# RadioAdapterBoardV4_0.net
KiCad netlist of a schematic drawn in EAGLE
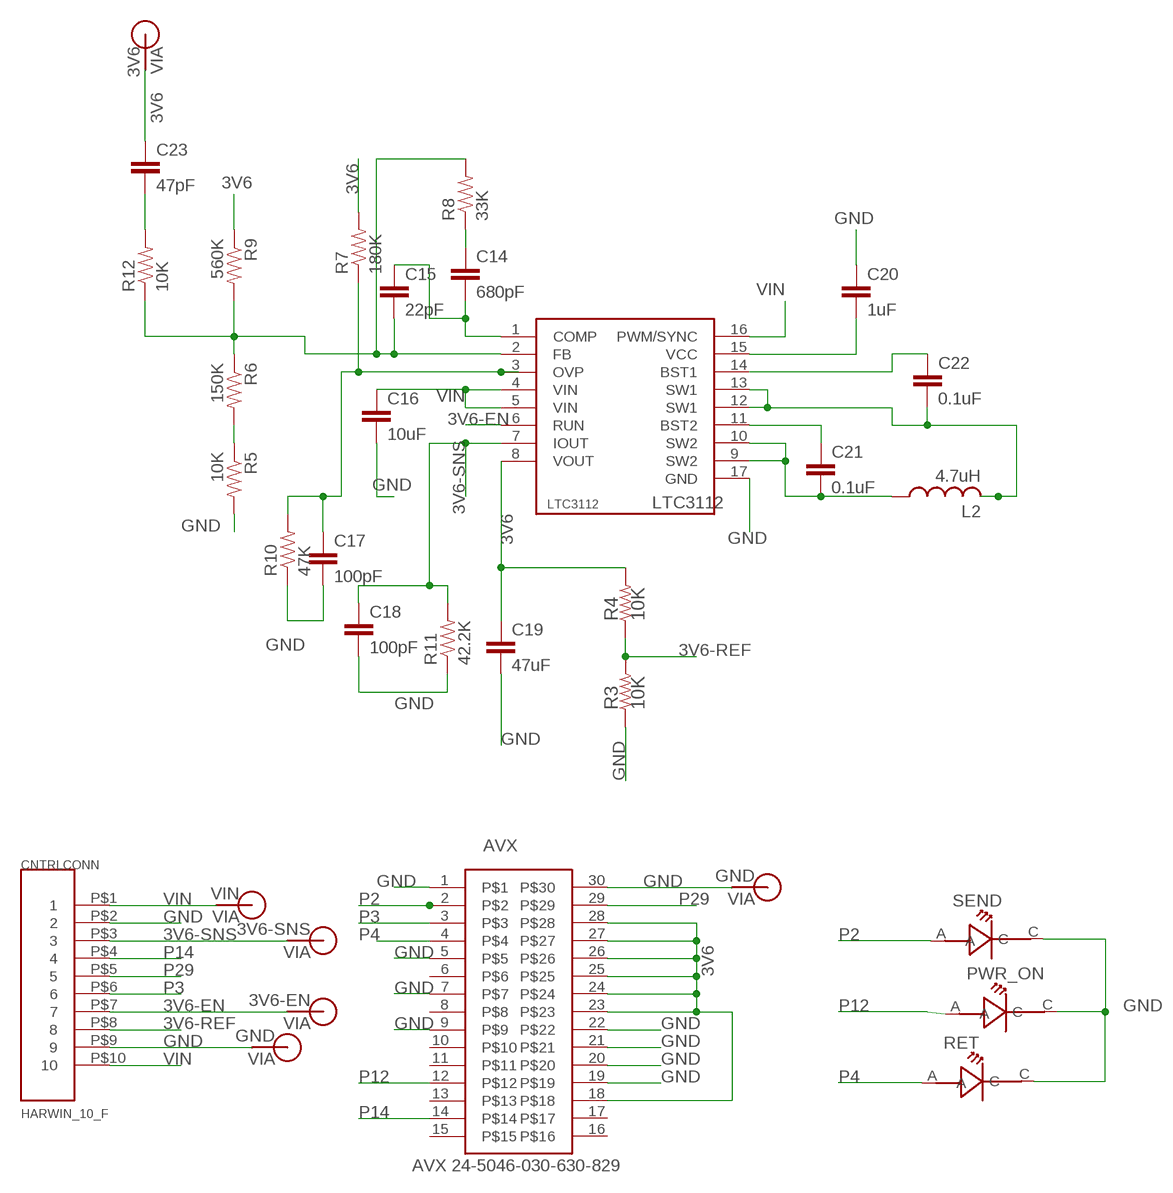
[diagram p0: schematic, sheet 1]

(export (version "E")
  (design (tool "Eeschema 10.0.6"))
  (components
    (comp (ref "AVX")
      (value "AVX-24-5046-030-630-829")
      (footprint "eagle-import:AVX-24-5046-630-829")
      (libsource (lib "eagle-import") (part "AVX-24-5046-030-630-829"))
    )
    (comp (ref "C14")
      (value "680pF")
      (footprint "eagle-import:0805")
      (libsource (lib "eagle-import") (part "CAP0805"))
    )
    (comp (ref "C15")
      (value "22pF")
      (footprint "eagle-import:0805")
      (libsource (lib "eagle-import") (part "CAP0805"))
    )
    (comp (ref "C16")
      (value "10uF")
      (footprint "eagle-import:0805")
      (libsource (lib "eagle-import") (part "CAP0805"))
    )
    (comp (ref "C17")
      (value "100pF")
      (footprint "eagle-import:0805")
      (libsource (lib "eagle-import") (part "CAP0805"))
    )
    (comp (ref "C18")
      (value "100pF")
      (footprint "eagle-import:0805")
      (libsource (lib "eagle-import") (part "CAP0805"))
    )
    (comp (ref "C19")
      (value "47uF")
      (footprint "eagle-import:0805")
      (libsource (lib "eagle-import") (part "CAP0805"))
    )
    (comp (ref "C20")
      (value "1uF")
      (footprint "eagle-import:0805")
      (libsource (lib "eagle-import") (part "CAP0805"))
    )
    (comp (ref "C21")
      (value "0.1uF")
      (footprint "eagle-import:0805")
      (libsource (lib "eagle-import") (part "CAP0805"))
    )
    (comp (ref "C22")
      (value "0.1uF")
      (footprint "eagle-import:0805")
      (libsource (lib "eagle-import") (part "CAP0805"))
    )
    (comp (ref "C23")
      (value "47pF")
      (footprint "eagle-import:0805")
      (libsource (lib "eagle-import") (part "CAP0805"))
    )
    (comp (ref "CNTRLCONN")
      (value "HARWIN_10_F")
      (footprint "eagle-import:HARWIN_DATAMATE_10_F")
      (libsource (lib "eagle-import") (part "HARWIN_10_F"))
    )
    (comp (ref "L2")
      (value "4.7uH")
      (footprint "eagle-import:L3225M")
      (libsource (lib "eagle-import") (part "L-USL3225M"))
    )
    (comp (ref "LTC3112")
      (value "LTC3112")
      (footprint "eagle-import:DHD16")
      (libsource (lib "eagle-import") (part "LTC3112"))
    )
    (comp (ref "PWR_ON")
      (value "LT-T673-Q1R2-25-Z")
      (footprint "eagle-import:PLCC-2")
      (libsource (lib "eagle-import") (part "LT-T673-Q1R2-25-Z"))
    )
    (comp (ref "R3")
      (value "10K")
      (footprint "eagle-import:0805")
      (libsource (lib "eagle-import") (part "RES0805"))
    )
    (comp (ref "R4")
      (value "10K")
      (footprint "eagle-import:0805")
      (libsource (lib "eagle-import") (part "RES0805"))
    )
    (comp (ref "R5")
      (value "10K")
      (footprint "eagle-import:0805")
      (libsource (lib "eagle-import") (part "RESISTOR"))
    )
    (comp (ref "R6")
      (value "150K")
      (footprint "eagle-import:0805")
      (libsource (lib "eagle-import") (part "RESISTOR"))
    )
    (comp (ref "R7")
      (value "180K")
      (footprint "eagle-import:0805")
      (libsource (lib "eagle-import") (part "RESISTOR"))
    )
    (comp (ref "R8")
      (value "33K")
      (footprint "eagle-import:0805")
      (libsource (lib "eagle-import") (part "RESISTOR"))
    )
    (comp (ref "R9")
      (value "560K")
      (footprint "eagle-import:0805")
      (libsource (lib "eagle-import") (part "RESISTOR"))
    )
    (comp (ref "R10")
      (value "47K")
      (footprint "eagle-import:0805")
      (libsource (lib "eagle-import") (part "RESISTOR"))
    )
    (comp (ref "R11")
      (value "42.2K")
      (footprint "eagle-import:0805")
      (libsource (lib "eagle-import") (part "RESISTOR"))
    )
    (comp (ref "R12")
      (value "10K")
      (footprint "eagle-import:0805")
      (libsource (lib "eagle-import") (part "RESISTOR"))
    )
    (comp (ref "RET")
      (value "LT-T673-Q1R2-25-Z")
      (footprint "eagle-import:PLCC-2")
      (libsource (lib "eagle-import") (part "LT-T673-Q1R2-25-Z"))
    )
    (comp (ref "SEND")
      (value "LT-T673-Q1R2-25-Z")
      (footprint "eagle-import:PLCC-2")
      (libsource (lib "eagle-import") (part "LT-T673-Q1R2-25-Z"))
    )
    (comp (ref "V1")
      (value "VIN")
      (footprint "eagle-import:VIA-60MIL-SQ")
      (libsource (lib "eagle-import") (part "VIA60MIL-SQ"))
    )
    (comp (ref "V2")
      (value "3V6-SNS")
      (footprint "eagle-import:VIA-60MIL-SQ")
      (libsource (lib "eagle-import") (part "VIA60MIL-SQ"))
    )
    (comp (ref "V3")
      (value "GND")
      (footprint "eagle-import:VIA-60MIL-SQ")
      (libsource (lib "eagle-import") (part "VIA60MIL-SQ"))
    )
    (comp (ref "V4")
      (value "GND")
      (footprint "eagle-import:VIA-60MIL-SQ")
      (libsource (lib "eagle-import") (part "VIA60MIL-SQ"))
    )
    (comp (ref "V5")
      (value "3V6")
      (footprint "eagle-import:VIA-60MIL-SQ")
      (libsource (lib "eagle-import") (part "VIA60MIL-SQ"))
    )
    (comp (ref "V6")
      (value "3V6-EN")
      (footprint "eagle-import:VIA-60MIL-SQ")
      (libsource (lib "eagle-import") (part "VIA60MIL-SQ"))
    )
  )
  (nets
    (net (code "1") (name "/3V6") (class "Default")
      (node (ref "AVX") (pin "18") (pinfunction "P$18_18") (pintype "bidirectional"))
      (node (ref "AVX") (pin "23") (pinfunction "P$23_23") (pintype "bidirectional"))
      (node (ref "AVX") (pin "24") (pinfunction "P$24_24") (pintype "bidirectional"))
      (node (ref "AVX") (pin "25") (pinfunction "P$25_25") (pintype "bidirectional"))
      (node (ref "AVX") (pin "26") (pinfunction "P$26_26") (pintype "bidirectional"))
      (node (ref "AVX") (pin "27") (pinfunction "P$27_27") (pintype "bidirectional"))
      (node (ref "AVX") (pin "28") (pinfunction "P$28_28") (pintype "bidirectional"))
      (node (ref "C19") (pin "1") (pinfunction "1_1") (pintype "passive"))
      (node (ref "C23") (pin "1") (pinfunction "1_1") (pintype "passive"))
      (node (ref "LTC3112") (pin "8") (pinfunction "VOUT_8") (pintype "bidirectional"))
      (node (ref "R4") (pin "2") (pinfunction "2_2") (pintype "passive"))
      (node (ref "R7") (pin "2") (pinfunction "2_2") (pintype "passive"))
      (node (ref "R9") (pin "1") (pinfunction "1_1") (pintype "passive"))
      (node (ref "V5") (pin "P$1") (pinfunction "P$1_P$1") (pintype "bidirectional"))
    )
    (net (code "2") (name "/3V6-EN") (class "Default")
      (node (ref "CNTRLCONN") (pin "P$7") (pinfunction "7_P$7") (pintype "bidirectional"))
      (node (ref "LTC3112") (pin "6") (pinfunction "RUN_6") (pintype "bidirectional"))
      (node (ref "V6") (pin "P$1") (pinfunction "P$1_P$1") (pintype "bidirectional"))
    )
    (net (code "3") (name "/3V6-REF") (class "Default")
      (node (ref "CNTRLCONN") (pin "P$8") (pinfunction "8_P$8") (pintype "bidirectional"))
      (node (ref "R3") (pin "2") (pinfunction "2_2") (pintype "passive"))
      (node (ref "R4") (pin "1") (pinfunction "1_1") (pintype "passive"))
    )
    (net (code "4") (name "/3V6-SNS") (class "Default")
      (node (ref "C18") (pin "1") (pinfunction "1_1") (pintype "passive"))
      (node (ref "CNTRLCONN") (pin "P$3") (pinfunction "3_P$3") (pintype "bidirectional"))
      (node (ref "LTC3112") (pin "7") (pinfunction "IOUT_7") (pintype "bidirectional"))
      (node (ref "R11") (pin "2") (pinfunction "2_2") (pintype "passive"))
      (node (ref "V2") (pin "P$1") (pinfunction "P$1_P$1") (pintype "bidirectional"))
    )
    (net (code "5") (name "/GND") (class "Default")
      (node (ref "AVX") (pin "1") (pinfunction "P$1_1") (pintype "bidirectional"))
      (node (ref "AVX") (pin "19") (pinfunction "P$19_19") (pintype "bidirectional"))
      (node (ref "AVX") (pin "20") (pinfunction "P$20_20") (pintype "bidirectional"))
      (node (ref "AVX") (pin "21") (pinfunction "P$21_21") (pintype "bidirectional"))
      (node (ref "AVX") (pin "22") (pinfunction "P$22_22") (pintype "bidirectional"))
      (node (ref "AVX") (pin "30") (pinfunction "P$30_30") (pintype "bidirectional"))
      (node (ref "AVX") (pin "5") (pinfunction "P$5_5") (pintype "bidirectional"))
      (node (ref "AVX") (pin "7") (pinfunction "P$7_7") (pintype "bidirectional"))
      (node (ref "AVX") (pin "9") (pinfunction "P$9_9") (pintype "bidirectional"))
      (node (ref "C16") (pin "2") (pinfunction "2_2") (pintype "passive"))
      (node (ref "C17") (pin "2") (pinfunction "2_2") (pintype "passive"))
      (node (ref "C18") (pin "2") (pinfunction "2_2") (pintype "passive"))
      (node (ref "C19") (pin "2") (pinfunction "2_2") (pintype "passive"))
      (node (ref "C20") (pin "1") (pinfunction "1_1") (pintype "passive"))
      (node (ref "CNTRLCONN") (pin "P$2") (pinfunction "2_P$2") (pintype "bidirectional"))
      (node (ref "CNTRLCONN") (pin "P$9") (pinfunction "9_P$9") (pintype "bidirectional"))
      (node (ref "LTC3112") (pin "17") (pinfunction "GND_17") (pintype "bidirectional"))
      (node (ref "PWR_ON") (pin "C") (pinfunction "C_C") (pintype "bidirectional"))
      (node (ref "R10") (pin "1") (pinfunction "1_1") (pintype "passive"))
      (node (ref "R11") (pin "1") (pinfunction "1_1") (pintype "passive"))
      (node (ref "R3") (pin "1") (pinfunction "1_1") (pintype "passive"))
      (node (ref "R5") (pin "2") (pinfunction "2_2") (pintype "passive"))
      (node (ref "RET") (pin "C") (pinfunction "C_C") (pintype "bidirectional"))
      (node (ref "SEND") (pin "C") (pinfunction "C_C") (pintype "bidirectional"))
      (node (ref "V3") (pin "P$1") (pinfunction "P$1_P$1") (pintype "bidirectional"))
      (node (ref "V4") (pin "P$1") (pinfunction "P$1_P$1") (pintype "bidirectional"))
    )
    (net (code "6") (name "/P2") (class "Default")
      (node (ref "AVX") (pin "2") (pinfunction "P$2_2") (pintype "bidirectional"))
      (node (ref "SEND") (pin "A") (pinfunction "A_A") (pintype "bidirectional"))
    )
    (net (code "7") (name "/P3") (class "Default")
      (node (ref "AVX") (pin "3") (pinfunction "P$3_3") (pintype "bidirectional"))
      (node (ref "CNTRLCONN") (pin "P$6") (pinfunction "6_P$6") (pintype "bidirectional"))
    )
    (net (code "8") (name "/P4") (class "Default")
      (node (ref "AVX") (pin "4") (pinfunction "P$4_4") (pintype "bidirectional"))
      (node (ref "RET") (pin "A") (pinfunction "A_A") (pintype "bidirectional"))
    )
    (net (code "9") (name "/P12") (class "Default")
      (node (ref "AVX") (pin "12") (pinfunction "P$12_12") (pintype "bidirectional"))
      (node (ref "PWR_ON") (pin "A") (pinfunction "A_A") (pintype "bidirectional"))
    )
    (net (code "10") (name "/P14") (class "Default")
      (node (ref "AVX") (pin "14") (pinfunction "P$14_14") (pintype "bidirectional"))
      (node (ref "CNTRLCONN") (pin "P$4") (pinfunction "4_P$4") (pintype "bidirectional"))
    )
    (net (code "11") (name "/P29") (class "Default")
      (node (ref "AVX") (pin "29") (pinfunction "P$29_29") (pintype "bidirectional"))
      (node (ref "CNTRLCONN") (pin "P$5") (pinfunction "5_P$5") (pintype "bidirectional"))
    )
    (net (code "12") (name "/VIN") (class "Default")
      (node (ref "C16") (pin "1") (pinfunction "1_1") (pintype "passive"))
      (node (ref "CNTRLCONN") (pin "P$1") (pinfunction "1_P$1") (pintype "bidirectional"))
      (node (ref "CNTRLCONN") (pin "P$10") (pinfunction "10_P$10") (pintype "bidirectional"))
      (node (ref "LTC3112") (pin "16") (pinfunction "PWM/SYNC_16") (pintype "bidirectional"))
      (node (ref "LTC3112") (pin "4") (pinfunction "VIN_4") (pintype "bidirectional"))
      (node (ref "LTC3112") (pin "5") (pinfunction "VIN_5") (pintype "bidirectional"))
      (node (ref "V1") (pin "P$1") (pinfunction "P$1_P$1") (pintype "bidirectional"))
    )
    (net (code "13") (name "Net-(C14-Pad1)") (class "Default")
      (node (ref "C14") (pin "1") (pinfunction "1_1") (pintype "passive"))
      (node (ref "R8") (pin "1") (pinfunction "1_1") (pintype "passive"))
    )
    (net (code "14") (name "Net-(C21-Pad2)") (class "Default")
      (node (ref "C21") (pin "2") (pinfunction "2_2") (pintype "passive"))
      (node (ref "L2") (pin "1") (pinfunction "1_1") (pintype "passive"))
      (node (ref "LTC3112") (pin "10") (pinfunction "SW2_10") (pintype "bidirectional"))
      (node (ref "LTC3112") (pin "9") (pinfunction "SW2_9") (pintype "bidirectional"))
    )
    (net (code "15") (name "Net-(C22-Pad2)") (class "Default")
      (node (ref "C22") (pin "2") (pinfunction "2_2") (pintype "passive"))
      (node (ref "L2") (pin "2") (pinfunction "2_2") (pintype "passive"))
      (node (ref "LTC3112") (pin "12") (pinfunction "SW1_12") (pintype "bidirectional"))
      (node (ref "LTC3112") (pin "13") (pinfunction "SW1_13") (pintype "bidirectional"))
    )
    (net (code "16") (name "Net-(C23-Pad2)") (class "Default")
      (node (ref "C23") (pin "2") (pinfunction "2_2") (pintype "passive"))
      (node (ref "R12") (pin "2") (pinfunction "2_2") (pintype "passive"))
    )
    (net (code "17") (name "Net-(LTC3112-BST1)") (class "Default")
      (node (ref "C22") (pin "1") (pinfunction "1_1") (pintype "passive"))
      (node (ref "LTC3112") (pin "14") (pinfunction "BST1_14") (pintype "bidirectional"))
    )
    (net (code "18") (name "Net-(LTC3112-BST2)") (class "Default")
      (node (ref "C21") (pin "1") (pinfunction "1_1") (pintype "passive"))
      (node (ref "LTC3112") (pin "11") (pinfunction "BST2_11") (pintype "bidirectional"))
    )
    (net (code "19") (name "Net-(LTC3112-COMP)") (class "Default")
      (node (ref "C14") (pin "2") (pinfunction "2_2") (pintype "passive"))
      (node (ref "C15") (pin "1") (pinfunction "1_1") (pintype "passive"))
      (node (ref "LTC3112") (pin "1") (pinfunction "COMP_1") (pintype "bidirectional"))
    )
    (net (code "20") (name "Net-(LTC3112-FB)") (class "Default")
      (node (ref "C15") (pin "2") (pinfunction "2_2") (pintype "passive"))
      (node (ref "LTC3112") (pin "2") (pinfunction "FB_2") (pintype "bidirectional"))
      (node (ref "R12") (pin "1") (pinfunction "1_1") (pintype "passive"))
      (node (ref "R6") (pin "1") (pinfunction "1_1") (pintype "passive"))
      (node (ref "R8") (pin "2") (pinfunction "2_2") (pintype "passive"))
      (node (ref "R9") (pin "2") (pinfunction "2_2") (pintype "passive"))
    )
    (net (code "21") (name "Net-(LTC3112-OVP)") (class "Default")
      (node (ref "C17") (pin "1") (pinfunction "1_1") (pintype "passive"))
      (node (ref "LTC3112") (pin "3") (pinfunction "OVP_3") (pintype "bidirectional"))
      (node (ref "R10") (pin "2") (pinfunction "2_2") (pintype "passive"))
      (node (ref "R7") (pin "1") (pinfunction "1_1") (pintype "passive"))
    )
    (net (code "22") (name "Net-(LTC3112-VCC)") (class "Default")
      (node (ref "C20") (pin "2") (pinfunction "2_2") (pintype "passive"))
      (node (ref "LTC3112") (pin "15") (pinfunction "VCC_15") (pintype "bidirectional"))
    )
    (net (code "23") (name "Net-(R5-Pad1)") (class "Default")
      (node (ref "R5") (pin "1") (pinfunction "1_1") (pintype "passive"))
      (node (ref "R6") (pin "2") (pinfunction "2_2") (pintype "passive"))
    )
    (net (code "24") (name "unconnected-(AVX-P$6-Pad6)") (class "Default")
      (node (ref "AVX") (pin "6") (pinfunction "P$6_6") (pintype "bidirectional"))
    )
    (net (code "25") (name "unconnected-(AVX-P$8-Pad8)") (class "Default")
      (node (ref "AVX") (pin "8") (pinfunction "P$8_8") (pintype "bidirectional"))
    )
    (net (code "26") (name "unconnected-(AVX-P$10-Pad10)") (class "Default")
      (node (ref "AVX") (pin "10") (pinfunction "P$10_10") (pintype "bidirectional"))
    )
    (net (code "27") (name "unconnected-(AVX-P$11-Pad11)") (class "Default")
      (node (ref "AVX") (pin "11") (pinfunction "P$11_11") (pintype "bidirectional"))
    )
    (net (code "28") (name "unconnected-(AVX-P$13-Pad13)") (class "Default")
      (node (ref "AVX") (pin "13") (pinfunction "P$13_13") (pintype "bidirectional"))
    )
    (net (code "29") (name "unconnected-(AVX-P$15-Pad15)") (class "Default")
      (node (ref "AVX") (pin "15") (pinfunction "P$15_15") (pintype "bidirectional"))
    )
    (net (code "30") (name "unconnected-(AVX-P$16-Pad16)") (class "Default")
      (node (ref "AVX") (pin "16") (pinfunction "P$16_16") (pintype "bidirectional"))
    )
    (net (code "31") (name "unconnected-(AVX-P$17-Pad17)") (class "Default")
      (node (ref "AVX") (pin "17") (pinfunction "P$17_17") (pintype "bidirectional"))
    )
  )
)
